# RPi-ILDA-DAC.net
KiCad netlist of a schematic drawn in EAGLE
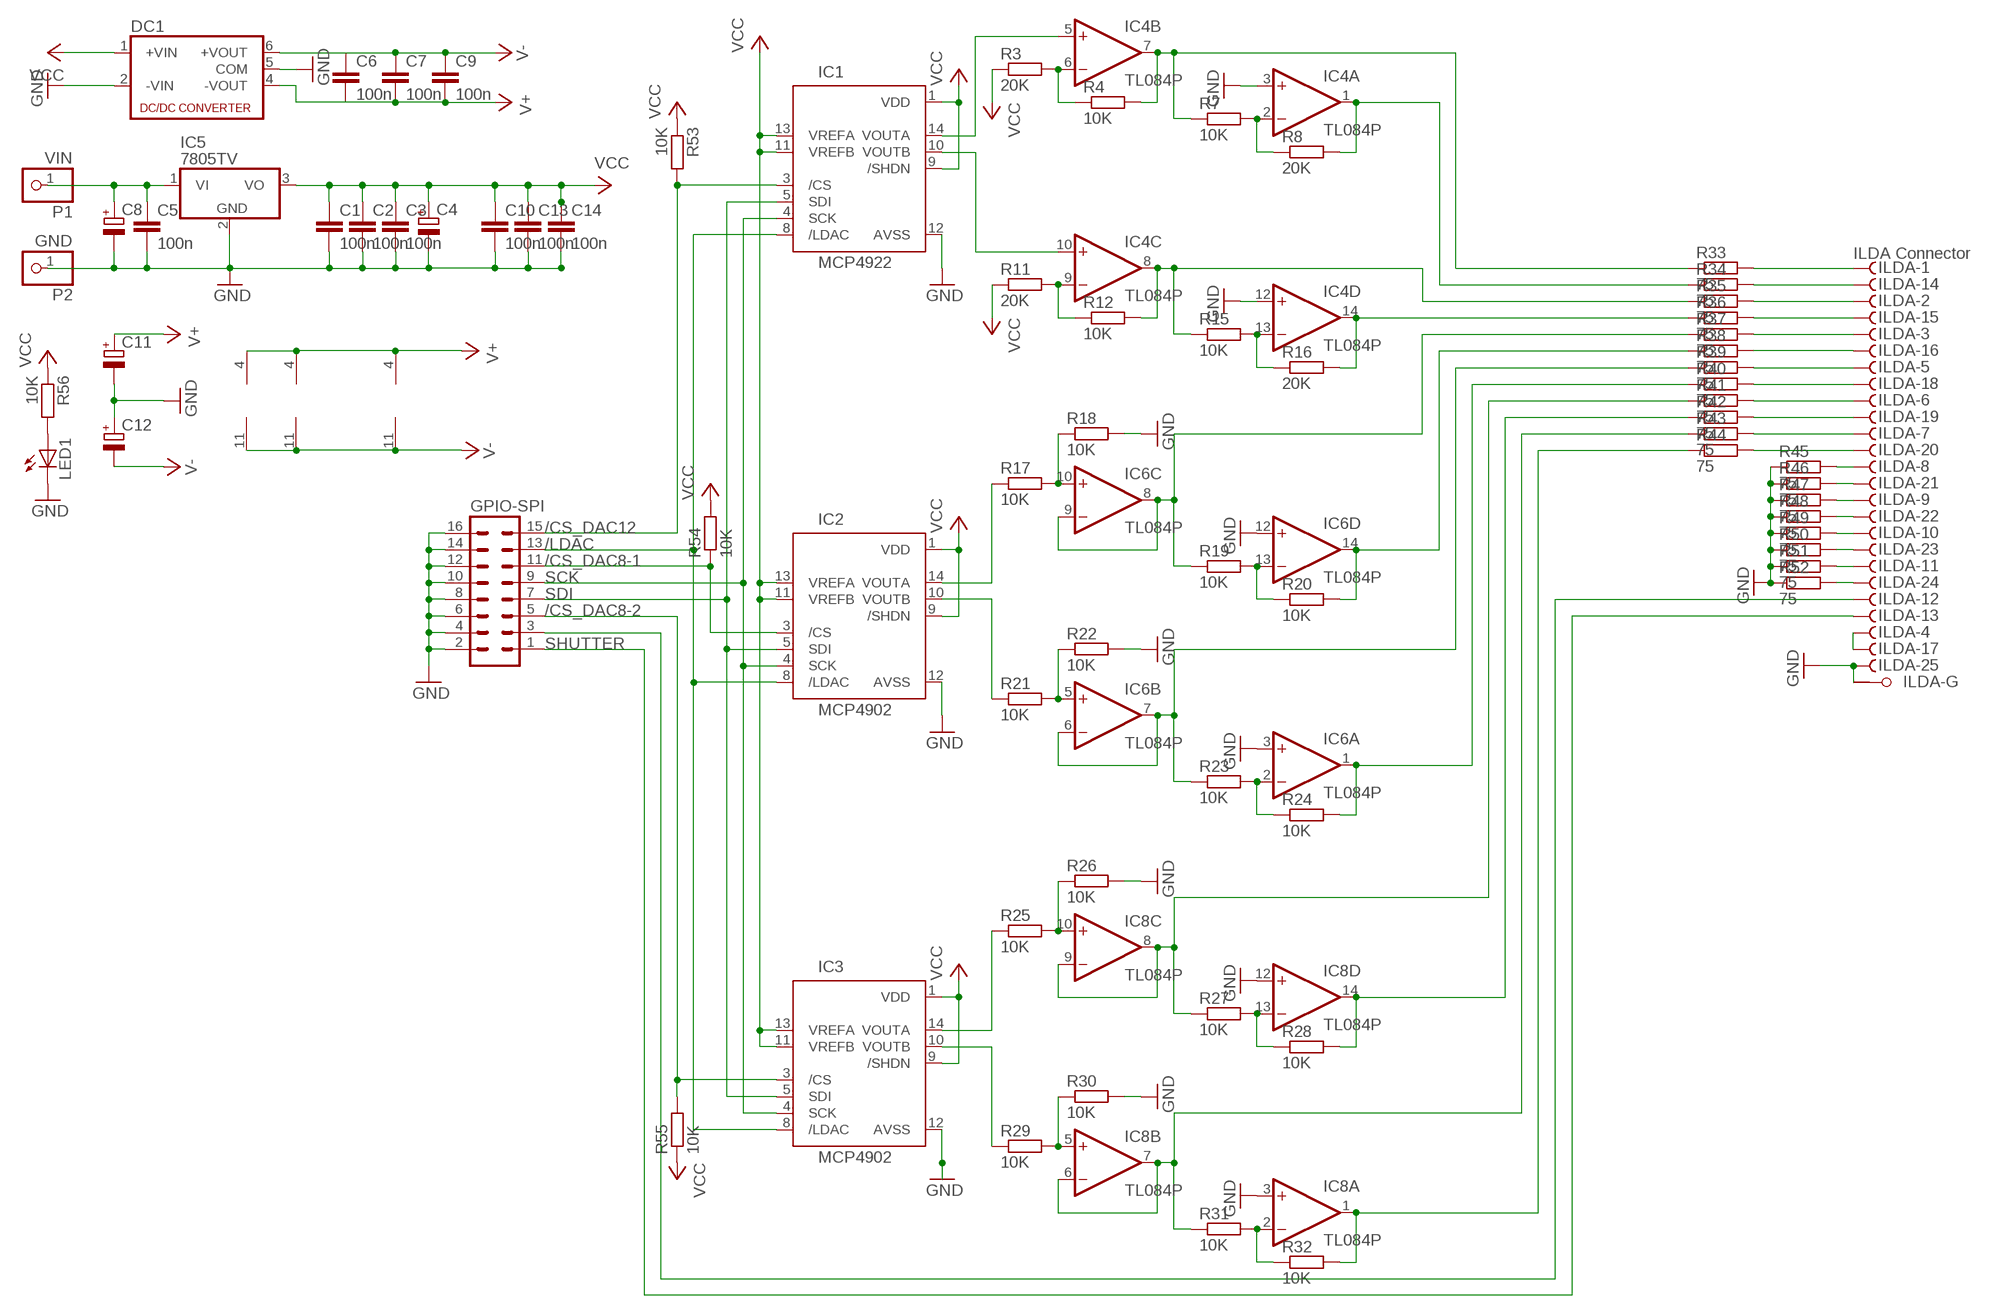
[diagram p0: schematic, sheet 1]

(export (version "E")
  (design (tool "Eeschema 10.0.6"))
  (components
    (comp (ref "C1")
      (value "100n")
      (footprint "eagle-import:C050-024X044")
      (libsource (lib "eagle-import") (part "C-EU050-024X044"))
    )
    (comp (ref "C2")
      (value "100n")
      (footprint "eagle-import:C050-024X044")
      (libsource (lib "eagle-import") (part "C-EU050-024X044"))
    )
    (comp (ref "C3")
      (value "100n")
      (footprint "eagle-import:C050-024X044")
      (libsource (lib "eagle-import") (part "C-EU050-024X044"))
    )
    (comp (ref "C4")
      (value "CPOL-EUE5-6")
      (footprint "eagle-import:E5-6")
      (libsource (lib "eagle-import") (part "CPOL-EUE5-6"))
    )
    (comp (ref "C5")
      (value "100n")
      (footprint "eagle-import:C050-024X044")
      (libsource (lib "eagle-import") (part "C-EU050-024X044"))
    )
    (comp (ref "C6")
      (value "100n")
      (footprint "eagle-import:C050-024X044")
      (libsource (lib "eagle-import") (part "C-EU050-024X044"))
    )
    (comp (ref "C7")
      (value "100n")
      (footprint "eagle-import:C050-024X044")
      (libsource (lib "eagle-import") (part "C-EU050-024X044"))
    )
    (comp (ref "C8")
      (value "CPOL-EUE5-6")
      (footprint "eagle-import:E5-6")
      (libsource (lib "eagle-import") (part "CPOL-EUE5-6"))
    )
    (comp (ref "C9")
      (value "100n")
      (footprint "eagle-import:C050-024X044")
      (libsource (lib "eagle-import") (part "C-EU050-024X044"))
    )
    (comp (ref "C10")
      (value "100n")
      (footprint "eagle-import:C050-024X044")
      (libsource (lib "eagle-import") (part "C-EU050-024X044"))
    )
    (comp (ref "C11")
      (value "CPOL-EUE5-6")
      (footprint "eagle-import:E5-6")
      (libsource (lib "eagle-import") (part "CPOL-EUE5-6"))
    )
    (comp (ref "C12")
      (value "CPOL-EUE5-6")
      (footprint "eagle-import:E5-6")
      (libsource (lib "eagle-import") (part "CPOL-EUE5-6"))
    )
    (comp (ref "C13")
      (value "100n")
      (footprint "eagle-import:C050-024X044")
      (libsource (lib "eagle-import") (part "C-EU050-024X044"))
    )
    (comp (ref "C14")
      (value "100n")
      (footprint "eagle-import:C050-024X044")
      (libsource (lib "eagle-import") (part "C-EU050-024X044"))
    )
    (comp (ref "DC1")
      (value "NMA")
      (footprint "eagle-import:NMA")
      (fields (field (name "MF") "C & D TECHNOLOGIES, INC") (field (name "MPN") "NMA0515SC"))
      (libsource (lib "eagle-import") (part "NMA"))
    )
    (comp (ref "GPIO-SPI")
      (value "MA08-2")
      (footprint "eagle-import:MA08-2")
      (libsource (lib "eagle-import") (part "MA08-2"))
    )
    (comp (ref "IC1")
      (value "MCP4922")
      (footprint "eagle-import:DIL14")
      (libsource (lib "eagle-import") (part "MCP4922"))
    )
    (comp (ref "IC2")
      (value "MCP4902")
      (footprint "eagle-import:DIL14")
      (libsource (lib "eagle-import") (part "MCP4922"))
    )
    (comp (ref "IC3")
      (value "MCP4902")
      (footprint "eagle-import:DIL14")
      (libsource (lib "eagle-import") (part "MCP4922"))
    )
    (comp (ref "IC4")
      (value "TL084P")
      (footprint "eagle-import:DIL14")
      (libsource (lib "eagle-import") (part "TL084P"))
    )
    (comp (ref "IC5")
      (value "7805TV")
      (footprint "eagle-import:TO220V")
      (libsource (lib "eagle-import") (part "78TV05"))
    )
    (comp (ref "IC6")
      (value "TL084P")
      (footprint "eagle-import:DIL14")
      (libsource (lib "eagle-import") (part "TL084P"))
    )
    (comp (ref "IC8")
      (value "TL084P")
      (footprint "eagle-import:DIL14")
      (libsource (lib "eagle-import") (part "TL084P"))
    )
    (comp (ref "ILDA")
      (value "ILDA Connector")
      (footprint "eagle-import:F25HP")
      (libsource (lib "eagle-import") (part "F25HPS"))
    )
    (comp (ref "LED1")
      (value "LED3MM")
      (footprint "eagle-import:LED3MM")
      (libsource (lib "eagle-import") (part "LED3MM"))
    )
    (comp (ref "P1")
      (value "VIN")
      (footprint "eagle-import:1X01")
      (libsource (lib "eagle-import") (part "PINHD-1X1"))
    )
    (comp (ref "P2")
      (value "GND")
      (footprint "eagle-import:1X01")
      (libsource (lib "eagle-import") (part "PINHD-1X1"))
    )
    (comp (ref "R3")
      (value "20K")
      (footprint "eagle-import:0204V")
      (libsource (lib "eagle-import") (part "R-EU_0204/2V"))
    )
    (comp (ref "R4")
      (value "10K")
      (footprint "eagle-import:0204V")
      (libsource (lib "eagle-import") (part "R-EU_0204/2V"))
    )
    (comp (ref "R7")
      (value "10K")
      (footprint "eagle-import:0204V")
      (libsource (lib "eagle-import") (part "R-EU_0204/2V"))
    )
    (comp (ref "R8")
      (value "20K")
      (footprint "eagle-import:0204V")
      (libsource (lib "eagle-import") (part "R-EU_0204/2V"))
    )
    (comp (ref "R11")
      (value "20K")
      (footprint "eagle-import:0204V")
      (libsource (lib "eagle-import") (part "R-EU_0204/2V"))
    )
    (comp (ref "R12")
      (value "10K")
      (footprint "eagle-import:0204V")
      (libsource (lib "eagle-import") (part "R-EU_0204/2V"))
    )
    (comp (ref "R15")
      (value "10K")
      (footprint "eagle-import:0204V")
      (libsource (lib "eagle-import") (part "R-EU_0204/2V"))
    )
    (comp (ref "R16")
      (value "20K")
      (footprint "eagle-import:0204V")
      (libsource (lib "eagle-import") (part "R-EU_0204/2V"))
    )
    (comp (ref "R17")
      (value "10K")
      (footprint "eagle-import:0204_5")
      (libsource (lib "eagle-import") (part "R-EU_0204/5"))
    )
    (comp (ref "R18")
      (value "10K")
      (footprint "eagle-import:0204V")
      (libsource (lib "eagle-import") (part "R-EU_0204/2V"))
    )
    (comp (ref "R19")
      (value "10K")
      (footprint "eagle-import:0204V")
      (libsource (lib "eagle-import") (part "R-EU_0204/2V"))
    )
    (comp (ref "R20")
      (value "10K")
      (footprint "eagle-import:0204V")
      (libsource (lib "eagle-import") (part "R-EU_0204/2V"))
    )
    (comp (ref "R21")
      (value "10K")
      (footprint "eagle-import:0204_5")
      (libsource (lib "eagle-import") (part "R-EU_0204/5"))
    )
    (comp (ref "R22")
      (value "10K")
      (footprint "eagle-import:0204V")
      (libsource (lib "eagle-import") (part "R-EU_0204/2V"))
    )
    (comp (ref "R23")
      (value "10K")
      (footprint "eagle-import:0204V")
      (libsource (lib "eagle-import") (part "R-EU_0204/2V"))
    )
    (comp (ref "R24")
      (value "10K")
      (footprint "eagle-import:0204V")
      (libsource (lib "eagle-import") (part "R-EU_0204/2V"))
    )
    (comp (ref "R25")
      (value "10K")
      (footprint "eagle-import:0204_5")
      (libsource (lib "eagle-import") (part "R-EU_0204/5"))
    )
    (comp (ref "R26")
      (value "10K")
      (footprint "eagle-import:0204V")
      (libsource (lib "eagle-import") (part "R-EU_0204/2V"))
    )
    (comp (ref "R27")
      (value "10K")
      (footprint "eagle-import:0204V")
      (libsource (lib "eagle-import") (part "R-EU_0204/2V"))
    )
    (comp (ref "R28")
      (value "10K")
      (footprint "eagle-import:0204V")
      (libsource (lib "eagle-import") (part "R-EU_0204/2V"))
    )
    (comp (ref "R29")
      (value "10K")
      (footprint "eagle-import:0204_5")
      (libsource (lib "eagle-import") (part "R-EU_0204/5"))
    )
    (comp (ref "R30")
      (value "10K")
      (footprint "eagle-import:0204V")
      (libsource (lib "eagle-import") (part "R-EU_0204/2V"))
    )
    (comp (ref "R31")
      (value "10K")
      (footprint "eagle-import:0204V")
      (libsource (lib "eagle-import") (part "R-EU_0204/2V"))
    )
    (comp (ref "R32")
      (value "10K")
      (footprint "eagle-import:0204V")
      (libsource (lib "eagle-import") (part "R-EU_0204/2V"))
    )
    (comp (ref "R33")
      (value "75")
      (footprint "eagle-import:0204_7")
      (libsource (lib "eagle-import") (part "R-EU_0204/7"))
    )
    (comp (ref "R34")
      (value "75")
      (footprint "eagle-import:0204_7")
      (libsource (lib "eagle-import") (part "R-EU_0204/7"))
    )
    (comp (ref "R35")
      (value "75")
      (footprint "eagle-import:0204_7")
      (libsource (lib "eagle-import") (part "R-EU_0204/7"))
    )
    (comp (ref "R36")
      (value "75")
      (footprint "eagle-import:0204_7")
      (libsource (lib "eagle-import") (part "R-EU_0204/7"))
    )
    (comp (ref "R37")
      (value "75")
      (footprint "eagle-import:0204_7")
      (libsource (lib "eagle-import") (part "R-EU_0204/7"))
    )
    (comp (ref "R38")
      (value "75")
      (footprint "eagle-import:0204_7")
      (libsource (lib "eagle-import") (part "R-EU_0204/7"))
    )
    (comp (ref "R39")
      (value "75")
      (footprint "eagle-import:0204_7")
      (libsource (lib "eagle-import") (part "R-EU_0204/7"))
    )
    (comp (ref "R40")
      (value "75")
      (footprint "eagle-import:0204_7")
      (libsource (lib "eagle-import") (part "R-EU_0204/7"))
    )
    (comp (ref "R41")
      (value "75")
      (footprint "eagle-import:0204_7")
      (libsource (lib "eagle-import") (part "R-EU_0204/7"))
    )
    (comp (ref "R42")
      (value "75")
      (footprint "eagle-import:0204_7")
      (libsource (lib "eagle-import") (part "R-EU_0204/7"))
    )
    (comp (ref "R43")
      (value "75")
      (footprint "eagle-import:0204_7")
      (libsource (lib "eagle-import") (part "R-EU_0204/7"))
    )
    (comp (ref "R44")
      (value "75")
      (footprint "eagle-import:0204_7")
      (libsource (lib "eagle-import") (part "R-EU_0204/7"))
    )
    (comp (ref "R45")
      (value "75")
      (footprint "eagle-import:0204V")
      (libsource (lib "eagle-import") (part "R-EU_0204/2V"))
    )
    (comp (ref "R46")
      (value "75")
      (footprint "eagle-import:0204V")
      (libsource (lib "eagle-import") (part "R-EU_0204/2V"))
    )
    (comp (ref "R47")
      (value "75")
      (footprint "eagle-import:0204V")
      (libsource (lib "eagle-import") (part "R-EU_0204/2V"))
    )
    (comp (ref "R48")
      (value "75")
      (footprint "eagle-import:0204V")
      (libsource (lib "eagle-import") (part "R-EU_0204/2V"))
    )
    (comp (ref "R49")
      (value "75")
      (footprint "eagle-import:0204V")
      (libsource (lib "eagle-import") (part "R-EU_0204/2V"))
    )
    (comp (ref "R50")
      (value "75")
      (footprint "eagle-import:0204V")
      (libsource (lib "eagle-import") (part "R-EU_0204/2V"))
    )
    (comp (ref "R51")
      (value "75")
      (footprint "eagle-import:0204V")
      (libsource (lib "eagle-import") (part "R-EU_0204/2V"))
    )
    (comp (ref "R52")
      (value "75")
      (footprint "eagle-import:0204V")
      (libsource (lib "eagle-import") (part "R-EU_0204/2V"))
    )
    (comp (ref "R53")
      (value "10K")
      (footprint "eagle-import:0204V")
      (libsource (lib "eagle-import") (part "R-EU_0204/2V"))
    )
    (comp (ref "R54")
      (value "10K")
      (footprint "eagle-import:0204V")
      (libsource (lib "eagle-import") (part "R-EU_0204/2V"))
    )
    (comp (ref "R55")
      (value "10K")
      (footprint "eagle-import:0204V")
      (libsource (lib "eagle-import") (part "R-EU_0204/2V"))
    )
    (comp (ref "R56")
      (value "10K")
      (footprint "eagle-import:0204_7")
      (libsource (lib "eagle-import") (part "R-EU_0204/7"))
    )
  )
  (nets
    (net (code "1") (name "/SCK") (class "Default")
      (node (ref "GPIO-SPI") (pin "9") (pinfunction "9_9") (pintype "passive"))
      (node (ref "IC1") (pin "4") (pinfunction "SCK_4") (pintype "input"))
      (node (ref "IC2") (pin "4") (pinfunction "SCK_4") (pintype "input"))
      (node (ref "IC3") (pin "4") (pinfunction "SCK_4") (pintype "input"))
    )
    (net (code "2") (name "/SDI") (class "Default")
      (node (ref "GPIO-SPI") (pin "7") (pinfunction "7_7") (pintype "passive"))
      (node (ref "IC1") (pin "5") (pinfunction "SDI_5") (pintype "input"))
      (node (ref "IC2") (pin "5") (pinfunction "SDI_5") (pintype "input"))
      (node (ref "IC3") (pin "5") (pinfunction "SDI_5") (pintype "input"))
    )
    (net (code "3") (name "/SHUTTER") (class "Default")
      (node (ref "GPIO-SPI") (pin "1") (pinfunction "1_1") (pintype "passive"))
      (node (ref "ILDA") (pin "13") (pinfunction "F_13") (pintype "passive"))
    )
    (net (code "4") (name "/{slash}CS_DAC8-1") (class "Default")
      (node (ref "GPIO-SPI") (pin "11") (pinfunction "11_11") (pintype "passive"))
      (node (ref "IC2") (pin "3") (pinfunction "/CS_3") (pintype "bidirectional"))
      (node (ref "R54") (pin "1") (pinfunction "1_1") (pintype "passive"))
    )
    (net (code "5") (name "/{slash}CS_DAC8-2") (class "Default")
      (node (ref "GPIO-SPI") (pin "5") (pinfunction "5_5") (pintype "passive"))
      (node (ref "IC3") (pin "3") (pinfunction "/CS_3") (pintype "bidirectional"))
      (node (ref "R55") (pin "2") (pinfunction "2_2") (pintype "passive"))
    )
    (net (code "6") (name "/{slash}CS_DAC12") (class "Default")
      (node (ref "GPIO-SPI") (pin "15") (pinfunction "15_15") (pintype "passive"))
      (node (ref "IC1") (pin "3") (pinfunction "/CS_3") (pintype "bidirectional"))
      (node (ref "R53") (pin "2") (pinfunction "2_2") (pintype "passive"))
    )
    (net (code "7") (name "/{slash}LDAC") (class "Default")
      (node (ref "GPIO-SPI") (pin "13") (pinfunction "13_13") (pintype "passive"))
      (node (ref "IC1") (pin "8") (pinfunction "/LDAC_8") (pintype "input"))
      (node (ref "IC2") (pin "8") (pinfunction "/LDAC_8") (pintype "input"))
      (node (ref "IC3") (pin "8") (pinfunction "/LDAC_8") (pintype "input"))
    )
    (net (code "8") (name "GND") (class "Default")
      (node (ref "C1") (pin "2") (pinfunction "2_2") (pintype "passive"))
      (node (ref "C10") (pin "2") (pinfunction "2_2") (pintype "passive"))
      (node (ref "C11") (pin "-") (pinfunction "-_-") (pintype "passive"))
      (node (ref "C12") (pin "+") (pinfunction "+_+") (pintype "passive"))
      (node (ref "C13") (pin "2") (pinfunction "2_2") (pintype "passive"))
      (node (ref "C14") (pin "2") (pinfunction "2_2") (pintype "passive"))
      (node (ref "C2") (pin "2") (pinfunction "2_2") (pintype "passive"))
      (node (ref "C3") (pin "2") (pinfunction "2_2") (pintype "passive"))
      (node (ref "C4") (pin "-") (pinfunction "-_-") (pintype "passive"))
      (node (ref "C5") (pin "2") (pinfunction "2_2") (pintype "passive"))
      (node (ref "C8") (pin "-") (pinfunction "-_-") (pintype "passive"))
      (node (ref "DC1") (pin "2") (pinfunction "-VIN_2") (pintype "passive"))
      (node (ref "DC1") (pin "5") (pinfunction "COM_5") (pintype "passive"))
      (node (ref "GPIO-SPI") (pin "10") (pinfunction "10_10") (pintype "passive"))
      (node (ref "GPIO-SPI") (pin "12") (pinfunction "12_12") (pintype "passive"))
      (node (ref "GPIO-SPI") (pin "14") (pinfunction "14_14") (pintype "passive"))
      (node (ref "GPIO-SPI") (pin "16") (pinfunction "16_16") (pintype "passive"))
      (node (ref "GPIO-SPI") (pin "2") (pinfunction "2_2") (pintype "passive"))
      (node (ref "GPIO-SPI") (pin "4") (pinfunction "4_4") (pintype "passive"))
      (node (ref "GPIO-SPI") (pin "6") (pinfunction "6_6") (pintype "passive"))
      (node (ref "GPIO-SPI") (pin "8") (pinfunction "8_8") (pintype "passive"))
      (node (ref "IC1") (pin "12") (pinfunction "AVSS_12") (pintype "power_in"))
      (node (ref "IC2") (pin "12") (pinfunction "AVSS_12") (pintype "power_in"))
      (node (ref "IC3") (pin "12") (pinfunction "AVSS_12") (pintype "power_in"))
      (node (ref "IC4") (pin "12") (pinfunction "+IN_12") (pintype "input"))
      (node (ref "IC4") (pin "3") (pinfunction "+IN_3") (pintype "input"))
      (node (ref "IC5") (pin "2") (pinfunction "GND_2") (pintype "passive"))
      (node (ref "IC6") (pin "12") (pinfunction "+IN_12") (pintype "input"))
      (node (ref "IC6") (pin "3") (pinfunction "+IN_3") (pintype "input"))
      (node (ref "IC8") (pin "12") (pinfunction "+IN_12") (pintype "input"))
      (node (ref "IC8") (pin "3") (pinfunction "+IN_3") (pintype "input"))
      (node (ref "ILDA") (pin "25") (pinfunction "F_25") (pintype "passive"))
      (node (ref "ILDA") (pin "G1") (pinfunction "G1_G1") (pintype "passive"))
      (node (ref "LED1") (pin "K") (pinfunction "C_K") (pintype "passive"))
      (node (ref "P2") (pin "1") (pinfunction "1_1") (pintype "passive"))
      (node (ref "R18") (pin "2") (pinfunction "2_2") (pintype "passive"))
      (node (ref "R22") (pin "2") (pinfunction "2_2") (pintype "passive"))
      (node (ref "R26") (pin "2") (pinfunction "2_2") (pintype "passive"))
      (node (ref "R30") (pin "2") (pinfunction "2_2") (pintype "passive"))
      (node (ref "R45") (pin "1") (pinfunction "1_1") (pintype "passive"))
      (node (ref "R46") (pin "1") (pinfunction "1_1") (pintype "passive"))
      (node (ref "R47") (pin "1") (pinfunction "1_1") (pintype "passive"))
      (node (ref "R48") (pin "1") (pinfunction "1_1") (pintype "passive"))
      (node (ref "R49") (pin "1") (pinfunction "1_1") (pintype "passive"))
      (node (ref "R50") (pin "1") (pinfunction "1_1") (pintype "passive"))
      (node (ref "R51") (pin "1") (pinfunction "1_1") (pintype "passive"))
      (node (ref "R52") (pin "1") (pinfunction "1_1") (pintype "passive"))
    )
    (net (code "9") (name "Net-(IC1-VOUTA)") (class "Default")
      (node (ref "IC1") (pin "14") (pinfunction "VOUTA_14") (pintype "output"))
      (node (ref "IC4") (pin "5") (pinfunction "+IN_5") (pintype "input"))
    )
    (net (code "10") (name "Net-(IC1-VOUTB)") (class "Default")
      (node (ref "IC1") (pin "10") (pinfunction "VOUTB_10") (pintype "output"))
      (node (ref "IC4") (pin "10") (pinfunction "+IN_10") (pintype "input"))
    )
    (net (code "11") (name "Net-(IC2-VOUTA)") (class "Default")
      (node (ref "IC2") (pin "14") (pinfunction "VOUTA_14") (pintype "output"))
      (node (ref "R17") (pin "1") (pinfunction "1_1") (pintype "passive"))
    )
    (net (code "12") (name "Net-(IC2-VOUTB)") (class "Default")
      (node (ref "IC2") (pin "10") (pinfunction "VOUTB_10") (pintype "output"))
      (node (ref "R21") (pin "1") (pinfunction "1_1") (pintype "passive"))
    )
    (net (code "13") (name "Net-(IC3-VOUTA)") (class "Default")
      (node (ref "IC3") (pin "14") (pinfunction "VOUTA_14") (pintype "output"))
      (node (ref "R25") (pin "1") (pinfunction "1_1") (pintype "passive"))
    )
    (net (code "14") (name "Net-(IC3-VOUTB)") (class "Default")
      (node (ref "IC3") (pin "10") (pinfunction "VOUTB_10") (pintype "output"))
      (node (ref "R29") (pin "1") (pinfunction "1_1") (pintype "passive"))
    )
    (net (code "15") (name "Net-(IC4A--IN)") (class "Default")
      (node (ref "IC4") (pin "2") (pinfunction "-IN_2") (pintype "input"))
      (node (ref "R7") (pin "2") (pinfunction "2_2") (pintype "passive"))
      (node (ref "R8") (pin "1") (pinfunction "1_1") (pintype "passive"))
    )
    (net (code "16") (name "Net-(IC4A-OUT)") (class "Default")
      (node (ref "IC4") (pin "1") (pinfunction "OUT_1") (pintype "output"))
      (node (ref "R34") (pin "1") (pinfunction "1_1") (pintype "passive"))
      (node (ref "R8") (pin "2") (pinfunction "2_2") (pintype "passive"))
    )
    (net (code "17") (name "Net-(IC4B--IN)") (class "Default")
      (node (ref "IC4") (pin "6") (pinfunction "-IN_6") (pintype "input"))
      (node (ref "R3") (pin "2") (pinfunction "2_2") (pintype "passive"))
      (node (ref "R4") (pin "1") (pinfunction "1_1") (pintype "passive"))
    )
    (net (code "18") (name "Net-(IC4B-OUT)") (class "Default")
      (node (ref "IC4") (pin "7") (pinfunction "OUT_7") (pintype "output"))
      (node (ref "R33") (pin "1") (pinfunction "1_1") (pintype "passive"))
      (node (ref "R4") (pin "2") (pinfunction "2_2") (pintype "passive"))
      (node (ref "R7") (pin "1") (pinfunction "1_1") (pintype "passive"))
    )
    (net (code "19") (name "Net-(IC4C--IN)") (class "Default")
      (node (ref "IC4") (pin "9") (pinfunction "-IN_9") (pintype "input"))
      (node (ref "R11") (pin "2") (pinfunction "2_2") (pintype "passive"))
      (node (ref "R12") (pin "1") (pinfunction "1_1") (pintype "passive"))
    )
    (net (code "20") (name "Net-(IC4C-OUT)") (class "Default")
      (node (ref "IC4") (pin "8") (pinfunction "OUT_8") (pintype "output"))
      (node (ref "R12") (pin "2") (pinfunction "2_2") (pintype "passive"))
      (node (ref "R15") (pin "1") (pinfunction "1_1") (pintype "passive"))
      (node (ref "R35") (pin "1") (pinfunction "1_1") (pintype "passive"))
    )
    (net (code "21") (name "Net-(IC4D--IN)") (class "Default")
      (node (ref "IC4") (pin "13") (pinfunction "-IN_13") (pintype "input"))
      (node (ref "R15") (pin "2") (pinfunction "2_2") (pintype "passive"))
      (node (ref "R16") (pin "1") (pinfunction "1_1") (pintype "passive"))
    )
    (net (code "22") (name "Net-(IC4D-OUT)") (class "Default")
      (node (ref "IC4") (pin "14") (pinfunction "OUT_14") (pintype "output"))
      (node (ref "R16") (pin "2") (pinfunction "2_2") (pintype "passive"))
      (node (ref "R36") (pin "1") (pinfunction "1_1") (pintype "passive"))
    )
    (net (code "23") (name "Net-(IC5-VI)") (class "Default")
      (node (ref "C5") (pin "1") (pinfunction "1_1") (pintype "passive"))
      (node (ref "C8") (pin "+") (pinfunction "+_+") (pintype "passive"))
      (node (ref "IC5") (pin "1") (pinfunction "VI_1") (pintype "input"))
      (node (ref "P1") (pin "1") (pinfunction "1_1") (pintype "passive"))
    )
    (net (code "24") (name "Net-(IC6A--IN)") (class "Default")
      (node (ref "IC6") (pin "2") (pinfunction "-IN_2") (pintype "input"))
      (node (ref "R23") (pin "2") (pinfunction "2_2") (pintype "passive"))
      (node (ref "R24") (pin "1") (pinfunction "1_1") (pintype "passive"))
    )
    (net (code "25") (name "Net-(IC6A-OUT)") (class "Default")
      (node (ref "IC6") (pin "1") (pinfunction "OUT_1") (pintype "output"))
      (node (ref "R24") (pin "2") (pinfunction "2_2") (pintype "passive"))
      (node (ref "R40") (pin "1") (pinfunction "1_1") (pintype "passive"))
    )
    (net (code "26") (name "Net-(IC6B-+IN)") (class "Default")
      (node (ref "IC6") (pin "5") (pinfunction "+IN_5") (pintype "input"))
      (node (ref "R21") (pin "2") (pinfunction "2_2") (pintype "passive"))
      (node (ref "R22") (pin "1") (pinfunction "1_1") (pintype "passive"))
    )
    (net (code "27") (name "Net-(IC6B--IN)") (class "Default")
      (node (ref "IC6") (pin "6") (pinfunction "-IN_6") (pintype "input"))
      (node (ref "IC6") (pin "7") (pinfunction "OUT_7") (pintype "output"))
      (node (ref "R23") (pin "1") (pinfunction "1_1") (pintype "passive"))
      (node (ref "R39") (pin "1") (pinfunction "1_1") (pintype "passive"))
    )
    (net (code "28") (name "Net-(IC6C-+IN)") (class "Default")
      (node (ref "IC6") (pin "10") (pinfunction "+IN_10") (pintype "input"))
      (node (ref "R17") (pin "2") (pinfunction "2_2") (pintype "passive"))
      (node (ref "R18") (pin "1") (pinfunction "1_1") (pintype "passive"))
    )
    (net (code "29") (name "Net-(IC6C--IN)") (class "Default")
      (node (ref "IC6") (pin "8") (pinfunction "OUT_8") (pintype "output"))
      (node (ref "IC6") (pin "9") (pinfunction "-IN_9") (pintype "input"))
      (node (ref "R19") (pin "1") (pinfunction "1_1") (pintype "passive"))
      (node (ref "R37") (pin "1") (pinfunction "1_1") (pintype "passive"))
    )
    (net (code "30") (name "Net-(IC6D--IN)") (class "Default")
      (node (ref "IC6") (pin "13") (pinfunction "-IN_13") (pintype "input"))
      (node (ref "R19") (pin "2") (pinfunction "2_2") (pintype "passive"))
      (node (ref "R20") (pin "1") (pinfunction "1_1") (pintype "passive"))
    )
    (net (code "31") (name "Net-(IC6D-OUT)") (class "Default")
      (node (ref "IC6") (pin "14") (pinfunction "OUT_14") (pintype "output"))
      (node (ref "R20") (pin "2") (pinfunction "2_2") (pintype "passive"))
      (node (ref "R38") (pin "1") (pinfunction "1_1") (pintype "passive"))
    )
    (net (code "32") (name "Net-(IC8A--IN)") (class "Default")
      (node (ref "IC8") (pin "2") (pinfunction "-IN_2") (pintype "input"))
      (node (ref "R31") (pin "2") (pinfunction "2_2") (pintype "passive"))
      (node (ref "R32") (pin "1") (pinfunction "1_1") (pintype "passive"))
    )
    (net (code "33") (name "Net-(IC8A-OUT)") (class "Default")
      (node (ref "IC8") (pin "1") (pinfunction "OUT_1") (pintype "output"))
      (node (ref "R32") (pin "2") (pinfunction "2_2") (pintype "passive"))
      (node (ref "R44") (pin "1") (pinfunction "1_1") (pintype "passive"))
    )
    (net (code "34") (name "Net-(IC8B-+IN)") (class "Default")
      (node (ref "IC8") (pin "5") (pinfunction "+IN_5") (pintype "input"))
      (node (ref "R29") (pin "2") (pinfunction "2_2") (pintype "passive"))
      (node (ref "R30") (pin "1") (pinfunction "1_1") (pintype "passive"))
    )
    (net (code "35") (name "Net-(IC8B--IN)") (class "Default")
      (node (ref "IC8") (pin "6") (pinfunction "-IN_6") (pintype "input"))
      (node (ref "IC8") (pin "7") (pinfunction "OUT_7") (pintype "output"))
      (node (ref "R31") (pin "1") (pinfunction "1_1") (pintype "passive"))
      (node (ref "R43") (pin "1") (pinfunction "1_1") (pintype "passive"))
    )
    (net (code "36") (name "Net-(IC8C-+IN)") (class "Default")
      (node (ref "IC8") (pin "10") (pinfunction "+IN_10") (pintype "input"))
      (node (ref "R25") (pin "2") (pinfunction "2_2") (pintype "passive"))
      (node (ref "R26") (pin "1") (pinfunction "1_1") (pintype "passive"))
    )
    (net (code "37") (name "Net-(IC8C--IN)") (class "Default")
      (node (ref "IC8") (pin "8") (pinfunction "OUT_8") (pintype "output"))
      (node (ref "IC8") (pin "9") (pinfunction "-IN_9") (pintype "input"))
      (node (ref "R27") (pin "1") (pinfunction "1_1") (pintype "passive"))
      (node (ref "R41") (pin "1") (pinfunction "1_1") (pintype "passive"))
    )
    (net (code "38") (name "Net-(IC8D--IN)") (class "Default")
      (node (ref "IC8") (pin "13") (pinfunction "-IN_13") (pintype "input"))
      (node (ref "R27") (pin "2") (pinfunction "2_2") (pintype "passive"))
      (node (ref "R28") (pin "1") (pinfunction "1_1") (pintype "passive"))
    )
    (net (code "39") (name "Net-(IC8D-OUT)") (class "Default")
      (node (ref "IC8") (pin "14") (pinfunction "OUT_14") (pintype "output"))
      (node (ref "R28") (pin "2") (pinfunction "2_2") (pintype "passive"))
      (node (ref "R42") (pin "1") (pinfunction "1_1") (pintype "passive"))
    )
    (net (code "40") (name "Net-(ILDAA-F)") (class "Default")
      (node (ref "ILDA") (pin "1") (pinfunction "F_1") (pintype "passive"))
      (node (ref "R33") (pin "2") (pinfunction "2_2") (pintype "passive"))
    )
    (net (code "41") (name "Net-(ILDAB-F)") (class "Default")
      (node (ref "ILDA") (pin "10") (pinfunction "F_10") (pintype "passive"))
      (node (ref "R49") (pin "2") (pinfunction "2_2") (pintype "passive"))
    )
    (net (code "42") (name "Net-(ILDAC-F)") (class "Default")
      (node (ref "ILDA") (pin "11") (pinfunction "F_11") (pintype "passive"))
      (node (ref "R51") (pin "2") (pinfunction "2_2") (pintype "passive"))
    )
    (net (code "43") (name "Net-(ILDAD-F)") (class "Default")
      (node (ref "GPIO-SPI") (pin "3") (pinfunction "3_3") (pintype "passive"))
      (node (ref "ILDA") (pin "12") (pinfunction "F_12") (pintype "passive"))
    )
    (net (code "44") (name "Net-(ILDAF-F)") (class "Default")
      (node (ref "ILDA") (pin "14") (pinfunction "F_14") (pintype "passive"))
      (node (ref "R34") (pin "2") (pinfunction "2_2") (pintype "passive"))
    )
    (net (code "45") (name "Net-(ILDAG-F)") (class "Default")
      (node (ref "ILDA") (pin "15") (pinfunction "F_15") (pintype "passive"))
      (node (ref "R36") (pin "2") (pinfunction "2_2") (pintype "passive"))
    )
    (net (code "46") (name "Net-(ILDAH-F)") (class "Default")
      (node (ref "ILDA") (pin "16") (pinfunction "F_16") (pintype "passive"))
      (node (ref "R38") (pin "2") (pinfunction "2_2") (pintype "passive"))
    )
    (net (code "47") (name "Net-(ILDAI-F)") (class "Default")
      (node (ref "ILDA") (pin "17") (pinfunction "F_17") (pintype "passive"))
      (node (ref "ILDA") (pin "4") (pinfunction "F_4") (pintype "passive"))
    )
    (net (code "48") (name "Net-(ILDAJ-F)") (class "Default")
      (node (ref "ILDA") (pin "18") (pinfunction "F_18") (pintype "passive"))
      (node (ref "R40") (pin "2") (pinfunction "2_2") (pintype "passive"))
    )
    (net (code "49") (name "Net-(ILDAK-F)") (class "Default")
      (node (ref "ILDA") (pin "19") (pinfunction "F_19") (pintype "passive"))
      (node (ref "R42") (pin "2") (pinfunction "2_2") (pintype "passive"))
    )
    (net (code "50") (name "Net-(ILDAL-F)") (class "Default")
      (node (ref "ILDA") (pin "2") (pinfunction "F_2") (pintype "passive"))
      (node (ref "R35") (pin "2") (pinfunction "2_2") (pintype "passive"))
    )
    (net (code "51") (name "Net-(ILDAM-F)") (class "Default")
      (node (ref "ILDA") (pin "20") (pinfunction "F_20") (pintype "passive"))
      (node (ref "R44") (pin "2") (pinfunction "2_2") (pintype "passive"))
    )
    (net (code "52") (name "Net-(ILDAN-F)") (class "Default")
      (node (ref "ILDA") (pin "21") (pinfunction "F_21") (pintype "passive"))
      (node (ref "R46") (pin "2") (pinfunction "2_2") (pintype "passive"))
    )
    (net (code "53") (name "Net-(ILDAO-F)") (class "Default")
      (node (ref "ILDA") (pin "22") (pinfunction "F_22") (pintype "passive"))
      (node (ref "R48") (pin "2") (pinfunction "2_2") (pintype "passive"))
    )
    (net (code "54") (name "Net-(ILDAP-F)") (class "Default")
      (node (ref "ILDA") (pin "23") (pinfunction "F_23") (pintype "passive"))
      (node (ref "R50") (pin "2") (pinfunction "2_2") (pintype "passive"))
    )
    (net (code "55") (name "Net-(ILDAQ-F)") (class "Default")
      (node (ref "ILDA") (pin "24") (pinfunction "F_24") (pintype "passive"))
      (node (ref "R52") (pin "2") (pinfunction "2_2") (pintype "passive"))
    )
    (net (code "56") (name "Net-(ILDAS-F)") (class "Default")
      (node (ref "ILDA") (pin "3") (pinfunction "F_3") (pintype "passive"))
      (node (ref "R37") (pin "2") (pinfunction "2_2") (pintype "passive"))
    )
    (net (code "57") (name "Net-(ILDAU-F)") (class "Default")
      (node (ref "ILDA") (pin "5") (pinfunction "F_5") (pintype "passive"))
      (node (ref "R39") (pin "2") (pinfunction "2_2") (pintype "passive"))
    )
    (net (code "58") (name "Net-(ILDAV-F)") (class "Default")
      (node (ref "ILDA") (pin "6") (pinfunction "F_6") (pintype "passive"))
      (node (ref "R41") (pin "2") (pinfunction "2_2") (pintype "passive"))
    )
    (net (code "59") (name "Net-(ILDAW-F)") (class "Default")
      (node (ref "ILDA") (pin "7") (pinfunction "F_7") (pintype "passive"))
      (node (ref "R43") (pin "2") (pinfunction "2_2") (pintype "passive"))
    )
    (net (code "60") (name "Net-(ILDAX-F)") (class "Default")
      (node (ref "ILDA") (pin "8") (pinfunction "F_8") (pintype "passive"))
      (node (ref "R45") (pin "2") (pinfunction "2_2") (pintype "passive"))
    )
    (net (code "61") (name "Net-(ILDAY-F)") (class "Default")
      (node (ref "ILDA") (pin "9") (pinfunction "F_9") (pintype "passive"))
      (node (ref "R47") (pin "2") (pinfunction "2_2") (pintype "passive"))
    )
    (net (code "62") (name "Net-(LED1-PadA)") (class "Default")
      (node (ref "LED1") (pin "A") (pinfunction "A_A") (pintype "passive"))
      (node (ref "R56") (pin "2") (pinfunction "2_2") (pintype "passive"))
    )
    (net (code "63") (name "V+") (class "Default")
      (node (ref "C11") (pin "+") (pinfunction "+_+") (pintype "passive"))
      (node (ref "C6") (pin "2") (pinfunction "2_2") (pintype "passive"))
      (node (ref "C7") (pin "2") (pinfunction "2_2") (pintype "passive"))
      (node (ref "C9") (pin "2") (pinfunction "2_2") (pintype "passive"))
      (node (ref "DC1") (pin "4") (pinfunction "-VOUT_4") (pintype "passive"))
      (node (ref "IC4") (pin "4") (pinfunction "V+_4") (pintype "power_in"))
      (node (ref "IC6") (pin "4") (pinfunction "V+_4") (pintype "power_in"))
      (node (ref "IC8") (pin "4") (pinfunction "V+_4") (pintype "power_in"))
    )
    (net (code "64") (name "V-") (class "Default")
      (node (ref "C12") (pin "-") (pinfunction "-_-") (pintype "passive"))
      (node (ref "C6") (pin "1") (pinfunction "1_1") (pintype "passive"))
      (node (ref "C7") (pin "1") (pinfunction "1_1") (pintype "passive"))
      (node (ref "C9") (pin "1") (pinfunction "1_1") (pintype "passive"))
      (node (ref "DC1") (pin "6") (pinfunction "+VOUT_6") (pintype "passive"))
      (node (ref "IC4") (pin "11") (pinfunction "V-_11") (pintype "power_in"))
      (node (ref "IC6") (pin "11") (pinfunction "V-_11") (pintype "power_in"))
      (node (ref "IC8") (pin "11") (pinfunction "V-_11") (pintype "power_in"))
    )
    (net (code "65") (name "VCC") (class "Default")
      (node (ref "C1") (pin "1") (pinfunction "1_1") (pintype "passive"))
      (node (ref "C10") (pin "1") (pinfunction "1_1") (pintype "passive"))
      (node (ref "C13") (pin "1") (pinfunction "1_1") (pintype "passive"))
      (node (ref "C14") (pin "1") (pinfunction "1_1") (pintype "passive"))
      (node (ref "C2") (pin "1") (pinfunction "1_1") (pintype "passive"))
      (node (ref "C3") (pin "1") (pinfunction "1_1") (pintype "passive"))
      (node (ref "C4") (pin "+") (pinfunction "+_+") (pintype "passive"))
      (node (ref "DC1") (pin "1") (pinfunction "+VIN_1") (pintype "passive"))
      (node (ref "IC1") (pin "1") (pinfunction "VDD_1") (pintype "power_in"))
      (node (ref "IC1") (pin "11") (pinfunction "VREFB_11") (pintype "bidirectional"))
      (node (ref "IC1") (pin "13") (pinfunction "VREFA_13") (pintype "input"))
      (node (ref "IC1") (pin "9") (pinfunction "/SHDN_9") (pintype "input"))
      (node (ref "IC2") (pin "1") (pinfunction "VDD_1") (pintype "power_in"))
      (node (ref "IC2") (pin "11") (pinfunction "VREFB_11") (pintype "bidirectional"))
      (node (ref "IC2") (pin "13") (pinfunction "VREFA_13") (pintype "input"))
      (node (ref "IC2") (pin "9") (pinfunction "/SHDN_9") (pintype "input"))
      (node (ref "IC3") (pin "1") (pinfunction "VDD_1") (pintype "power_in"))
      (node (ref "IC3") (pin "11") (pinfunction "VREFB_11") (pintype "bidirectional"))
      (node (ref "IC3") (pin "13") (pinfunction "VREFA_13") (pintype "input"))
      (node (ref "IC3") (pin "9") (pinfunction "/SHDN_9") (pintype "input"))
      (node (ref "IC5") (pin "3") (pinfunction "VO_3") (pintype "passive"))
      (node (ref "R11") (pin "1") (pinfunction "1_1") (pintype "passive"))
      (node (ref "R3") (pin "1") (pinfunction "1_1") (pintype "passive"))
      (node (ref "R53") (pin "1") (pinfunction "1_1") (pintype "passive"))
      (node (ref "R54") (pin "2") (pinfunction "2_2") (pintype "passive"))
      (node (ref "R55") (pin "1") (pinfunction "1_1") (pintype "passive"))
      (node (ref "R56") (pin "1") (pinfunction "1_1") (pintype "passive"))
    )
    (net (code "66") (name "unconnected-(ILDA-PadG2)") (class "Default")
      (node (ref "ILDA") (pin "G2") (pinfunction "G2_G2") (pintype "passive"))
    )
  )
)
